# radio-v1_0.net
KiCad netlist of a schematic drawn in EAGLE
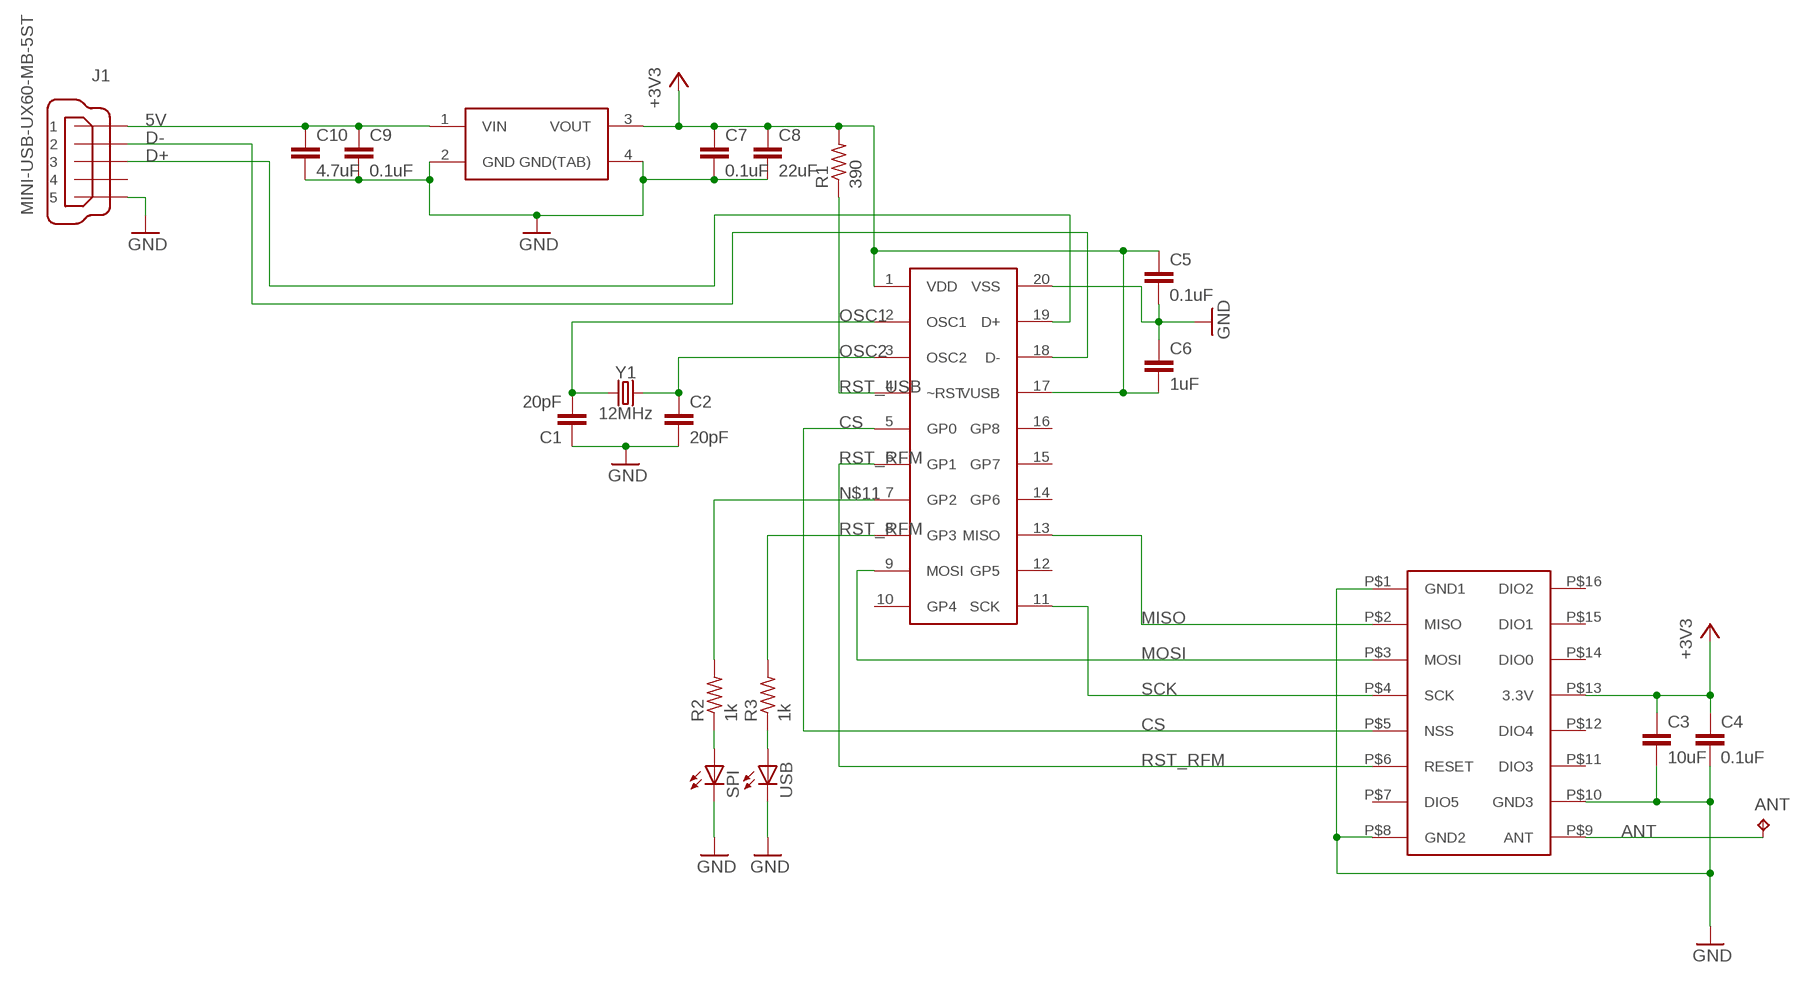
[diagram p0: schematic, sheet 1]

(export (version "E")
  (design (tool "Eeschema 10.0.6"))
  (components
    (comp (ref "ANT")
      (value "TPPAD1-17Y")
      (footprint "eagle-import:P1-17Y")
      (libsource (lib "eagle-import") (part "TPPAD1-17Y"))
    )
    (comp (ref "C1")
      (value "20pF")
      (footprint "eagle-import:C0603")
      (libsource (lib "eagle-import") (part "C-EUC0603"))
    )
    (comp (ref "C2")
      (value "20pF")
      (footprint "eagle-import:C0603")
      (libsource (lib "eagle-import") (part "C-EUC0603"))
    )
    (comp (ref "C3")
      (value "10uF")
      (footprint "eagle-import:C0603")
      (libsource (lib "eagle-import") (part "C-EUC0603"))
    )
    (comp (ref "C4")
      (value "0.1uF")
      (footprint "eagle-import:C0603")
      (libsource (lib "eagle-import") (part "C-EUC0603"))
    )
    (comp (ref "C5")
      (value "0.1uF")
      (footprint "eagle-import:C0603")
      (libsource (lib "eagle-import") (part "C-EUC0603"))
    )
    (comp (ref "C6")
      (value "1uF")
      (footprint "eagle-import:C0603")
      (libsource (lib "eagle-import") (part "C-EUC0603"))
    )
    (comp (ref "C7")
      (value "0.1uF")
      (footprint "eagle-import:C0603")
      (libsource (lib "eagle-import") (part "C-EUC0603"))
    )
    (comp (ref "C8")
      (value "22uF")
      (footprint "eagle-import:C0603")
      (libsource (lib "eagle-import") (part "C-EUC0603"))
    )
    (comp (ref "C9")
      (value "0.1uF")
      (footprint "eagle-import:C0603")
      (libsource (lib "eagle-import") (part "C-EUC0603"))
    )
    (comp (ref "C10")
      (value "4.7uF")
      (footprint "eagle-import:C0603")
      (libsource (lib "eagle-import") (part "C-EUC0603"))
    )
    (comp (ref "J1")
      (value "MINI-USB-UX60-MB-5ST")
      (footprint "eagle-import:UX60-MB-5ST")
      (libsource (lib "eagle-import") (part "MINI-USB-UX60-MB-5ST"))
    )
    (comp (ref "R1")
      (value "390")
      (footprint "eagle-import:R0603")
      (libsource (lib "eagle-import") (part "R-US_R0603"))
    )
    (comp (ref "R2")
      (value "1k")
      (footprint "eagle-import:R0603")
      (libsource (lib "eagle-import") (part "R-US_R0603"))
    )
    (comp (ref "R3")
      (value "1k")
      (footprint "eagle-import:R0603")
      (libsource (lib "eagle-import") (part "R-US_R0603"))
    )
    (comp (ref "SPI")
      (value "LED3MM")
      (footprint "eagle-import:LED3MM")
      (libsource (lib "eagle-import") (part "LED3MM"))
    )
    (comp (ref "U1")
      (value "MCP2210")
      (footprint "eagle-import:SOIC20S")
      (libsource (lib "eagle-import") (part "MCP2210"))
    )
    (comp (ref "U2")
      (value "RFM69HCW")
      (footprint "eagle-import:RFM69HCW")
      (libsource (lib "eagle-import") (part "RFM69HCW"))
    )
    (comp (ref "U3")
      (value "MCP1825S_DBMCP1825S_DB")
      (footprint "eagle-import:SOT223")
      (libsource (lib "eagle-import") (part "MCP1825S_DBMCP1825S_DB"))
    )
    (comp (ref "USB")
      (value "LED3MM")
      (footprint "eagle-import:LED3MM")
      (libsource (lib "eagle-import") (part "LED3MM"))
    )
    (comp (ref "Y1")
      (value "12MHz")
      (footprint "eagle-import:HC49UP")
      (libsource (lib "eagle-import") (part "CRYSTAL-8MHZSMD-HC49UP"))
    )
  )
  (nets
    (net (code "1") (name "+3V3") (class "Default")
      (node (ref "C3") (pin "1") (pinfunction "1_1") (pintype "passive"))
      (node (ref "C4") (pin "1") (pinfunction "1_1") (pintype "passive"))
      (node (ref "C5") (pin "1") (pinfunction "1_1") (pintype "passive"))
      (node (ref "C6") (pin "2") (pinfunction "2_2") (pintype "passive"))
      (node (ref "C7") (pin "1") (pinfunction "1_1") (pintype "passive"))
      (node (ref "C8") (pin "1") (pinfunction "1_1") (pintype "passive"))
      (node (ref "R1") (pin "2") (pinfunction "2_2") (pintype "passive"))
      (node (ref "U1") (pin "1") (pinfunction "VDD_1") (pintype "power_in"))
      (node (ref "U1") (pin "17") (pinfunction "VUSB_17") (pintype "power_in"))
      (node (ref "U2") (pin "P$13") (pinfunction "3.3V_P$13") (pintype "power_in"))
      (node (ref "U3") (pin "3") (pinfunction "VOUT_3") (pintype "power_in"))
    )
    (net (code "2") (name "/5V") (class "Default")
      (node (ref "C10") (pin "1") (pinfunction "1_1") (pintype "passive"))
      (node (ref "C9") (pin "1") (pinfunction "1_1") (pintype "passive"))
      (node (ref "J1") (pin "1") (pinfunction "1_1") (pintype "input"))
      (node (ref "U3") (pin "1") (pinfunction "VIN_1") (pintype "power_in"))
    )
    (net (code "3") (name "/ANT") (class "Default")
      (node (ref "ANT") (pin "TP") (pinfunction "TP_TP") (pintype "input"))
      (node (ref "U2") (pin "P$9") (pinfunction "ANT_P$9") (pintype "bidirectional"))
    )
    (net (code "4") (name "/CS") (class "Default")
      (node (ref "U1") (pin "5") (pinfunction "GP0_5") (pintype "bidirectional"))
      (node (ref "U2") (pin "P$5") (pinfunction "NSS_P$5") (pintype "input"))
    )
    (net (code "5") (name "/D+") (class "Default")
      (node (ref "J1") (pin "3") (pinfunction "3_3") (pintype "input"))
      (node (ref "U1") (pin "19") (pinfunction "D+_19") (pintype "bidirectional"))
    )
    (net (code "6") (name "/D-") (class "Default")
      (node (ref "J1") (pin "2") (pinfunction "2_2") (pintype "input"))
      (node (ref "U1") (pin "18") (pinfunction "D-_18") (pintype "bidirectional"))
    )
    (net (code "7") (name "/MISO") (class "Default")
      (node (ref "U1") (pin "13") (pinfunction "MISO_13") (pintype "bidirectional"))
      (node (ref "U2") (pin "P$2") (pinfunction "MISO_P$2") (pintype "bidirectional"))
    )
    (net (code "8") (name "/MOSI") (class "Default")
      (node (ref "U1") (pin "9") (pinfunction "MOSI_9") (pintype "bidirectional"))
      (node (ref "U2") (pin "P$3") (pinfunction "MOSI_P$3") (pintype "bidirectional"))
    )
    (net (code "9") (name "/N$11") (class "Default")
      (node (ref "R2") (pin "2") (pinfunction "2_2") (pintype "passive"))
      (node (ref "U1") (pin "7") (pinfunction "GP2_7") (pintype "bidirectional"))
    )
    (net (code "10") (name "/OSC1") (class "Default")
      (node (ref "C1") (pin "2") (pinfunction "2_2") (pintype "passive"))
      (node (ref "U1") (pin "2") (pinfunction "OSC1_2") (pintype "bidirectional"))
      (node (ref "Y1") (pin "1") (pinfunction "1_1") (pintype "passive"))
    )
    (net (code "11") (name "/OSC2") (class "Default")
      (node (ref "C2") (pin "1") (pinfunction "1_1") (pintype "passive"))
      (node (ref "U1") (pin "3") (pinfunction "OSC2_3") (pintype "bidirectional"))
      (node (ref "Y1") (pin "2") (pinfunction "2_2") (pintype "passive"))
    )
    (net (code "12") (name "/RST_RFM") (class "Default")
      (node (ref "U1") (pin "6") (pinfunction "GP1_6") (pintype "bidirectional"))
      (node (ref "U2") (pin "P$6") (pinfunction "RESET_P$6") (pintype "input"))
    )
    (net (code "13") (name "/RST_USB") (class "Default")
      (node (ref "R1") (pin "1") (pinfunction "1_1") (pintype "passive"))
      (node (ref "U1") (pin "4") (pinfunction "~{RST}_4") (pintype "bidirectional"))
    )
    (net (code "14") (name "/SCK") (class "Default")
      (node (ref "U1") (pin "11") (pinfunction "SCK_11") (pintype "bidirectional"))
      (node (ref "U2") (pin "P$4") (pinfunction "SCK_P$4") (pintype "bidirectional"))
    )
    (net (code "15") (name "GND") (class "Default")
      (node (ref "C1") (pin "1") (pinfunction "1_1") (pintype "passive"))
      (node (ref "C10") (pin "2") (pinfunction "2_2") (pintype "passive"))
      (node (ref "C2") (pin "2") (pinfunction "2_2") (pintype "passive"))
      (node (ref "C3") (pin "2") (pinfunction "2_2") (pintype "passive"))
      (node (ref "C4") (pin "2") (pinfunction "2_2") (pintype "passive"))
      (node (ref "C5") (pin "2") (pinfunction "2_2") (pintype "passive"))
      (node (ref "C6") (pin "1") (pinfunction "1_1") (pintype "passive"))
      (node (ref "C7") (pin "2") (pinfunction "2_2") (pintype "passive"))
      (node (ref "C8") (pin "2") (pinfunction "2_2") (pintype "passive"))
      (node (ref "C9") (pin "2") (pinfunction "2_2") (pintype "passive"))
      (node (ref "J1") (pin "5") (pinfunction "5_5") (pintype "input"))
      (node (ref "SPI") (pin "K") (pinfunction "C_K") (pintype "passive"))
      (node (ref "U1") (pin "20") (pinfunction "VSS_20") (pintype "power_in"))
      (node (ref "U2") (pin "P$1") (pinfunction "GND1_P$1") (pintype "power_in"))
      (node (ref "U2") (pin "P$10") (pinfunction "GND3_P$10") (pintype "power_in"))
      (node (ref "U2") (pin "P$8") (pinfunction "GND2_P$8") (pintype "power_in"))
      (node (ref "U3") (pin "2") (pinfunction "GND_2") (pintype "power_in"))
      (node (ref "U3") (pin "4") (pinfunction "GND(TAB)_4") (pintype "power_in"))
      (node (ref "USB") (pin "K") (pinfunction "C_K") (pintype "passive"))
    )
    (net (code "16") (name "Net-(R2-Pad1)") (class "Default")
      (node (ref "R2") (pin "1") (pinfunction "1_1") (pintype "passive"))
      (node (ref "SPI") (pin "A") (pinfunction "A_A") (pintype "passive"))
    )
    (net (code "17") (name "Net-(R3-Pad1)") (class "Default")
      (node (ref "R3") (pin "1") (pinfunction "1_1") (pintype "passive"))
      (node (ref "USB") (pin "A") (pinfunction "A_A") (pintype "passive"))
    )
    (net (code "18") (name "Net-(U1-GP3)") (class "Default")
      (node (ref "R3") (pin "2") (pinfunction "2_2") (pintype "passive"))
      (node (ref "U1") (pin "8") (pinfunction "GP3_8") (pintype "bidirectional"))
    )
    (net (code "19") (name "unconnected-(J1-Pad4)") (class "Default")
      (node (ref "J1") (pin "4") (pinfunction "4_4") (pintype "input"))
    )
    (net (code "20") (name "unconnected-(U1-GP4-Pad10)") (class "Default")
      (node (ref "U1") (pin "10") (pinfunction "GP4_10") (pintype "bidirectional"))
    )
    (net (code "21") (name "unconnected-(U1-GP5-Pad12)") (class "Default")
      (node (ref "U1") (pin "12") (pinfunction "GP5_12") (pintype "bidirectional"))
    )
    (net (code "22") (name "unconnected-(U1-GP6-Pad14)") (class "Default")
      (node (ref "U1") (pin "14") (pinfunction "GP6_14") (pintype "bidirectional"))
    )
    (net (code "23") (name "unconnected-(U1-GP7-Pad15)") (class "Default")
      (node (ref "U1") (pin "15") (pinfunction "GP7_15") (pintype "bidirectional"))
    )
    (net (code "24") (name "unconnected-(U1-GP8-Pad16)") (class "Default")
      (node (ref "U1") (pin "16") (pinfunction "GP8_16") (pintype "bidirectional"))
    )
    (net (code "25") (name "unconnected-(U2-DIO0-PadP$14)") (class "Default")
      (node (ref "U2") (pin "P$14") (pinfunction "DIO0_P$14") (pintype "bidirectional"))
    )
    (net (code "26") (name "unconnected-(U2-DIO1-PadP$15)") (class "Default")
      (node (ref "U2") (pin "P$15") (pinfunction "DIO1_P$15") (pintype "bidirectional"))
    )
    (net (code "27") (name "unconnected-(U2-DIO2-PadP$16)") (class "Default")
      (node (ref "U2") (pin "P$16") (pinfunction "DIO2_P$16") (pintype "bidirectional"))
    )
    (net (code "28") (name "unconnected-(U2-DIO3-PadP$11)") (class "Default")
      (node (ref "U2") (pin "P$11") (pinfunction "DIO3_P$11") (pintype "bidirectional"))
    )
    (net (code "29") (name "unconnected-(U2-DIO4-PadP$12)") (class "Default")
      (node (ref "U2") (pin "P$12") (pinfunction "DIO4_P$12") (pintype "bidirectional"))
    )
    (net (code "30") (name "unconnected-(U2-DIO5-PadP$7)") (class "Default")
      (node (ref "U2") (pin "P$7") (pinfunction "DIO5_P$7") (pintype "bidirectional"))
    )
  )
)
